# Sheet_1_2021-03-30.net
KiCad netlist of a schematic drawn in Altium Designer
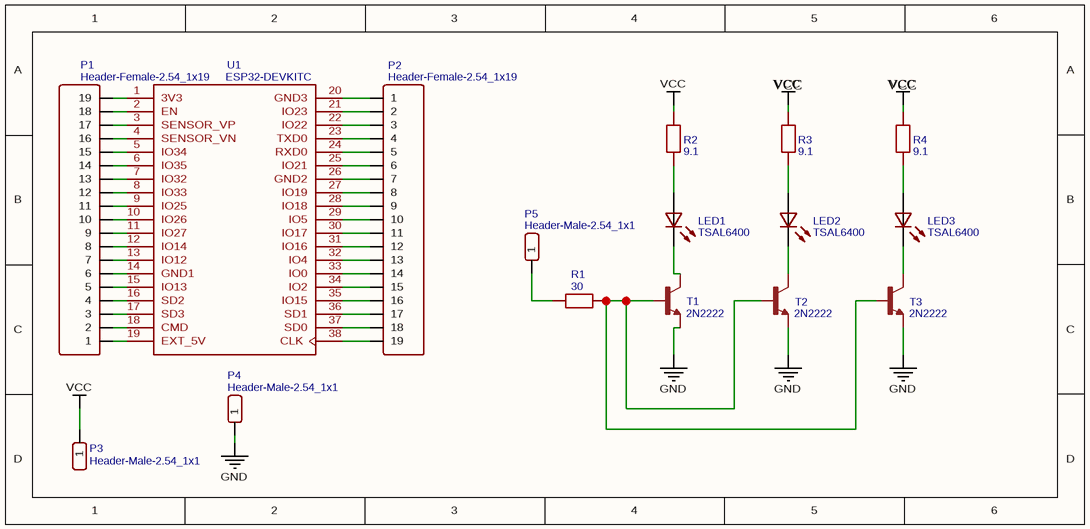
[diagram p0: Sheet_1_2021-03-30.schdoc]

(export (version "E")
  (design (tool "Eeschema 10.0.6"))
  (components
    (comp (ref "LED1")
      (value "TSAL6400")
      (fields (field (name "BOM_SUPPLIER PART") "C94857") (field (name "CONTRIBUTOR") "Russell Bryson"))
      (libsource (lib "altium-import") (part "root_3_TSAL6400_"))
    )
    (comp (ref "LED2")
      (value "TSAL6400")
      (fields (field (name "BOM_SUPPLIER PART") "C94857") (field (name "CONTRIBUTOR") "Russell Bryson"))
      (libsource (lib "altium-import") (part "root_3_TSAL6400_"))
    )
    (comp (ref "LED3")
      (value "TSAL6400")
      (fields (field (name "BOM_SUPPLIER PART") "C94857") (field (name "CONTRIBUTOR") "Russell Bryson"))
      (libsource (lib "altium-import") (part "root_3_TSAL6400_"))
    )
    (comp (ref "P1")
      (value "Header-Female-2.54_1x19")
      (fields
        (field (name "BOM_MANUFACTURER PART") "2.54mm 1*20P Female header")
        (field (name "BOM_SUPPLIER PART") "C50984")
        (field (name "CONTRIBUTOR") "erikhjertholm")
      )
      (libsource (lib "altium-import") (part "root_2_Header-Female-2.54_1x19_"))
    )
    (comp (ref "P2")
      (value "Header-Female-2.54_1x19")
      (fields
        (field (name "BOM_MANUFACTURER PART") "2.54mm 1*20P Female header")
        (field (name "BOM_SUPPLIER PART") "C50984")
        (field (name "CONTRIBUTOR") "erikhjertholm")
      )
      (libsource (lib "altium-import") (part "root_0_Header-Female-2.54_1x19_"))
    )
    (comp (ref "P3")
      (value "Header-Male-2.54_1x1")
      (fields (field (name "BOM_SUPPLIER PART") "C81276"))
      (libsource (lib "altium-import") (part "root_3_Header-Male-2.54_1x1_"))
    )
    (comp (ref "P4")
      (value "Header-Male-2.54_1x1")
      (fields (field (name "BOM_SUPPLIER PART") "C81276"))
      (libsource (lib "altium-import") (part "root_1_Header-Male-2.54_1x1_"))
    )
    (comp (ref "P5")
      (value "Header-Male-2.54_1x1")
      (fields (field (name "BOM_SUPPLIER PART") "C81276"))
      (libsource (lib "altium-import") (part "root_1_Header-Male-2.54_1x1_"))
    )
    (comp (ref "R1") (value "30") (libsource (lib "altium-import") (part "root_0_30_")))
    (comp (ref "R2") (value "9.1") (libsource (lib "altium-import") (part "root_1_9.1_")))
    (comp (ref "R3") (value "9.1") (libsource (lib "altium-import") (part "root_1_9.1_")))
    (comp (ref "R4") (value "9.1") (libsource (lib "altium-import") (part "root_1_9.1_")))
    (comp (ref "T1")
      (value "2N2222")
      (fields (field (name "CONTRIBUTOR") "Adafruit"))
      (libsource (lib "altium-import") (part "root_0_2N2222_"))
    )
    (comp (ref "T2")
      (value "2N2222")
      (fields (field (name "CONTRIBUTOR") "Adafruit"))
      (libsource (lib "altium-import") (part "root_0_2N2222_"))
    )
    (comp (ref "T3")
      (value "2N2222")
      (fields (field (name "CONTRIBUTOR") "Adafruit"))
      (libsource (lib "altium-import") (part "root_0_2N2222_"))
    )
    (comp (ref "U1")
      (value "ESP32-DEVKITC")
      (fields (field (name "CONTRIBUTOR") "PatriceBarret"))
      (libsource (lib "altium-import") (part "root_0_ESP32-DEVKITC_"))
    )
  )
  (nets
    (net (code "1") (name "GND") (class "Default")
      (node (ref "P4") (pin "1") (pinfunction "1_1") (pintype "passive"))
      (node (ref "T1") (pin "E") (pinfunction "E_E") (pintype "passive"))
      (node (ref "T2") (pin "E") (pinfunction "E_E") (pintype "passive"))
      (node (ref "T3") (pin "E") (pinfunction "E_E") (pintype "passive"))
    )
    (net (code "2") (name "Net-(LED1-A)") (class "Default")
      (node (ref "LED1") (pin "1") (pinfunction "A_1") (pintype "passive"))
      (node (ref "R2") (pin "1") (pinfunction "1_1") (pintype "passive"))
    )
    (net (code "3") (name "Net-(LED1-C)") (class "Default")
      (node (ref "LED1") (pin "2") (pinfunction "C_2") (pintype "passive"))
      (node (ref "T1") (pin "C") (pinfunction "C_C") (pintype "passive"))
    )
    (net (code "4") (name "Net-(LED2-A)") (class "Default")
      (node (ref "LED2") (pin "1") (pinfunction "A_1") (pintype "passive"))
      (node (ref "R3") (pin "1") (pinfunction "1_1") (pintype "passive"))
    )
    (net (code "5") (name "Net-(LED2-C)") (class "Default")
      (node (ref "LED2") (pin "2") (pinfunction "C_2") (pintype "passive"))
      (node (ref "T2") (pin "C") (pinfunction "C_C") (pintype "passive"))
    )
    (net (code "6") (name "Net-(LED3-A)") (class "Default")
      (node (ref "LED3") (pin "1") (pinfunction "A_1") (pintype "passive"))
      (node (ref "R4") (pin "1") (pinfunction "1_1") (pintype "passive"))
    )
    (net (code "7") (name "Net-(LED3-C)") (class "Default")
      (node (ref "LED3") (pin "2") (pinfunction "C_2") (pintype "passive"))
      (node (ref "T3") (pin "C") (pinfunction "C_C") (pintype "passive"))
    )
    (net (code "8") (name "Net-(P5-Pad1)") (class "Default")
      (node (ref "P5") (pin "1") (pinfunction "1_1") (pintype "passive"))
      (node (ref "R1") (pin "1") (pinfunction "1_1") (pintype "passive"))
    )
    (net (code "9") (name "Net-(R1-Pad2)") (class "Default")
      (node (ref "R1") (pin "2") (pinfunction "2_2") (pintype "passive"))
      (node (ref "T1") (pin "B") (pinfunction "B_B") (pintype "passive"))
      (node (ref "T2") (pin "B") (pinfunction "B_B") (pintype "passive"))
      (node (ref "T3") (pin "B") (pinfunction "B_B") (pintype "passive"))
    )
    (net (code "10") (name "Net-(U1-3V3)") (class "Default")
      (node (ref "P1") (pin "19") (pinfunction "19_19") (pintype "passive"))
      (node (ref "U1") (pin "1") (pinfunction "3V3_1") (pintype "passive"))
    )
    (net (code "11") (name "Net-(U1-CLK)") (class "Default")
      (node (ref "P2") (pin "19") (pinfunction "19_19") (pintype "passive"))
      (node (ref "U1") (pin "38") (pinfunction "CLK_38") (pintype "passive"))
    )
    (net (code "12") (name "Net-(U1-CMD)") (class "Default")
      (node (ref "P1") (pin "2") (pinfunction "2_2") (pintype "passive"))
      (node (ref "U1") (pin "18") (pinfunction "CMD_18") (pintype "passive"))
    )
    (net (code "13") (name "Net-(U1-EN)") (class "Default")
      (node (ref "P1") (pin "18") (pinfunction "18_18") (pintype "passive"))
      (node (ref "U1") (pin "2") (pinfunction "EN_2") (pintype "passive"))
    )
    (net (code "14") (name "Net-(U1-EXT_5V)") (class "Default")
      (node (ref "P1") (pin "1") (pinfunction "1_1") (pintype "passive"))
      (node (ref "U1") (pin "19") (pinfunction "EXT_5V_19") (pintype "passive"))
    )
    (net (code "15") (name "Net-(U1-GND1)") (class "Default")
      (node (ref "P1") (pin "6") (pinfunction "6_6") (pintype "passive"))
      (node (ref "U1") (pin "14") (pinfunction "GND1_14") (pintype "passive"))
    )
    (net (code "16") (name "Net-(U1-GND2)") (class "Default")
      (node (ref "P2") (pin "7") (pinfunction "7_7") (pintype "passive"))
      (node (ref "U1") (pin "26") (pinfunction "GND2_26") (pintype "passive"))
    )
    (net (code "17") (name "Net-(U1-GND3)") (class "Default")
      (node (ref "P2") (pin "1") (pinfunction "1_1") (pintype "passive"))
      (node (ref "U1") (pin "20") (pinfunction "GND3_20") (pintype "passive"))
    )
    (net (code "18") (name "Net-(U1-IO0)") (class "Default")
      (node (ref "P2") (pin "14") (pinfunction "14_14") (pintype "passive"))
      (node (ref "U1") (pin "33") (pinfunction "IO0_33") (pintype "passive"))
    )
    (net (code "19") (name "Net-(U1-IO2)") (class "Default")
      (node (ref "P2") (pin "15") (pinfunction "15_15") (pintype "passive"))
      (node (ref "U1") (pin "34") (pinfunction "IO2_34") (pintype "passive"))
    )
    (net (code "20") (name "Net-(U1-IO4)") (class "Default")
      (node (ref "P2") (pin "13") (pinfunction "13_13") (pintype "passive"))
      (node (ref "U1") (pin "32") (pinfunction "IO4_32") (pintype "passive"))
    )
    (net (code "21") (name "Net-(U1-IO5)") (class "Default")
      (node (ref "P2") (pin "10") (pinfunction "10_10") (pintype "passive"))
      (node (ref "U1") (pin "29") (pinfunction "IO5_29") (pintype "passive"))
    )
    (net (code "22") (name "Net-(U1-IO12)") (class "Default")
      (node (ref "P1") (pin "7") (pinfunction "7_7") (pintype "passive"))
      (node (ref "U1") (pin "13") (pinfunction "IO12_13") (pintype "passive"))
    )
    (net (code "23") (name "Net-(U1-IO13)") (class "Default")
      (node (ref "P1") (pin "5") (pinfunction "5_5") (pintype "passive"))
      (node (ref "U1") (pin "15") (pinfunction "IO13_15") (pintype "passive"))
    )
    (net (code "24") (name "Net-(U1-IO14)") (class "Default")
      (node (ref "P1") (pin "8") (pinfunction "8_8") (pintype "passive"))
      (node (ref "U1") (pin "12") (pinfunction "IO14_12") (pintype "passive"))
    )
    (net (code "25") (name "Net-(U1-IO15)") (class "Default")
      (node (ref "P2") (pin "16") (pinfunction "16_16") (pintype "passive"))
      (node (ref "U1") (pin "35") (pinfunction "IO15_35") (pintype "passive"))
    )
    (net (code "26") (name "Net-(U1-IO16)") (class "Default")
      (node (ref "P2") (pin "12") (pinfunction "12_12") (pintype "passive"))
      (node (ref "U1") (pin "31") (pinfunction "IO16_31") (pintype "passive"))
    )
    (net (code "27") (name "Net-(U1-IO17)") (class "Default")
      (node (ref "P2") (pin "11") (pinfunction "11_11") (pintype "passive"))
      (node (ref "U1") (pin "30") (pinfunction "IO17_30") (pintype "passive"))
    )
    (net (code "28") (name "Net-(U1-IO18)") (class "Default")
      (node (ref "P2") (pin "9") (pinfunction "9_9") (pintype "passive"))
      (node (ref "U1") (pin "28") (pinfunction "IO18_28") (pintype "passive"))
    )
    (net (code "29") (name "Net-(U1-IO19)") (class "Default")
      (node (ref "P2") (pin "8") (pinfunction "8_8") (pintype "passive"))
      (node (ref "U1") (pin "27") (pinfunction "IO19_27") (pintype "passive"))
    )
    (net (code "30") (name "Net-(U1-IO21)") (class "Default")
      (node (ref "P2") (pin "6") (pinfunction "6_6") (pintype "passive"))
      (node (ref "U1") (pin "25") (pinfunction "IO21_25") (pintype "passive"))
    )
    (net (code "31") (name "Net-(U1-IO22)") (class "Default")
      (node (ref "P2") (pin "3") (pinfunction "3_3") (pintype "passive"))
      (node (ref "U1") (pin "22") (pinfunction "IO22_22") (pintype "passive"))
    )
    (net (code "32") (name "Net-(U1-IO23)") (class "Default")
      (node (ref "P2") (pin "2") (pinfunction "2_2") (pintype "passive"))
      (node (ref "U1") (pin "21") (pinfunction "IO23_21") (pintype "passive"))
    )
    (net (code "33") (name "Net-(U1-IO25)") (class "Default")
      (node (ref "P1") (pin "11") (pinfunction "11_11") (pintype "passive"))
      (node (ref "U1") (pin "9") (pinfunction "IO25_9") (pintype "passive"))
    )
    (net (code "34") (name "Net-(U1-IO26)") (class "Default")
      (node (ref "P1") (pin "10") (pinfunction "10_10") (pintype "passive"))
      (node (ref "U1") (pin "10") (pinfunction "IO26_10") (pintype "passive"))
    )
    (net (code "35") (name "Net-(U1-IO27)") (class "Default")
      (node (ref "P1") (pin "9") (pinfunction "9_9") (pintype "passive"))
      (node (ref "U1") (pin "11") (pinfunction "IO27_11") (pintype "passive"))
    )
    (net (code "36") (name "Net-(U1-IO32)") (class "Default")
      (node (ref "P1") (pin "13") (pinfunction "13_13") (pintype "passive"))
      (node (ref "U1") (pin "7") (pinfunction "IO32_7") (pintype "passive"))
    )
    (net (code "37") (name "Net-(U1-IO33)") (class "Default")
      (node (ref "P1") (pin "12") (pinfunction "12_12") (pintype "passive"))
      (node (ref "U1") (pin "8") (pinfunction "IO33_8") (pintype "passive"))
    )
    (net (code "38") (name "Net-(U1-IO34)") (class "Default")
      (node (ref "P1") (pin "15") (pinfunction "15_15") (pintype "passive"))
      (node (ref "U1") (pin "5") (pinfunction "IO34_5") (pintype "passive"))
    )
    (net (code "39") (name "Net-(U1-IO35)") (class "Default")
      (node (ref "P1") (pin "14") (pinfunction "14_14") (pintype "passive"))
      (node (ref "U1") (pin "6") (pinfunction "IO35_6") (pintype "passive"))
    )
    (net (code "40") (name "Net-(U1-RXD0)") (class "Default")
      (node (ref "P2") (pin "5") (pinfunction "5_5") (pintype "passive"))
      (node (ref "U1") (pin "24") (pinfunction "RXD0_24") (pintype "passive"))
    )
    (net (code "41") (name "Net-(U1-SD0)") (class "Default")
      (node (ref "P2") (pin "18") (pinfunction "18_18") (pintype "passive"))
      (node (ref "U1") (pin "37") (pinfunction "SD0_37") (pintype "passive"))
    )
    (net (code "42") (name "Net-(U1-SD1)") (class "Default")
      (node (ref "P2") (pin "17") (pinfunction "17_17") (pintype "passive"))
      (node (ref "U1") (pin "36") (pinfunction "SD1_36") (pintype "passive"))
    )
    (net (code "43") (name "Net-(U1-SD2)") (class "Default")
      (node (ref "P1") (pin "4") (pinfunction "4_4") (pintype "passive"))
      (node (ref "U1") (pin "16") (pinfunction "SD2_16") (pintype "passive"))
    )
    (net (code "44") (name "Net-(U1-SD3)") (class "Default")
      (node (ref "P1") (pin "3") (pinfunction "3_3") (pintype "passive"))
      (node (ref "U1") (pin "17") (pinfunction "SD3_17") (pintype "passive"))
    )
    (net (code "45") (name "Net-(U1-SENSOR_VN)") (class "Default")
      (node (ref "P1") (pin "16") (pinfunction "16_16") (pintype "passive"))
      (node (ref "U1") (pin "4") (pinfunction "SENSOR_VN_4") (pintype "passive"))
    )
    (net (code "46") (name "Net-(U1-SENSOR_VP)") (class "Default")
      (node (ref "P1") (pin "17") (pinfunction "17_17") (pintype "passive"))
      (node (ref "U1") (pin "3") (pinfunction "SENSOR_VP_3") (pintype "passive"))
    )
    (net (code "47") (name "Net-(U1-TXD0)") (class "Default")
      (node (ref "P2") (pin "4") (pinfunction "4_4") (pintype "passive"))
      (node (ref "U1") (pin "23") (pinfunction "TXD0_23") (pintype "passive"))
    )
    (net (code "48") (name "VCC") (class "Default")
      (node (ref "P3") (pin "1") (pinfunction "1_1") (pintype "passive"))
      (node (ref "R2") (pin "2") (pinfunction "2_2") (pintype "passive"))
      (node (ref "R3") (pin "2") (pinfunction "2_2") (pintype "passive"))
      (node (ref "R4") (pin "2") (pinfunction "2_2") (pintype "passive"))
    )
  )
)
